# 5_cyber60-mxhs_periferals.net
KiCad netlist of a schematic drawn in Altium Designer
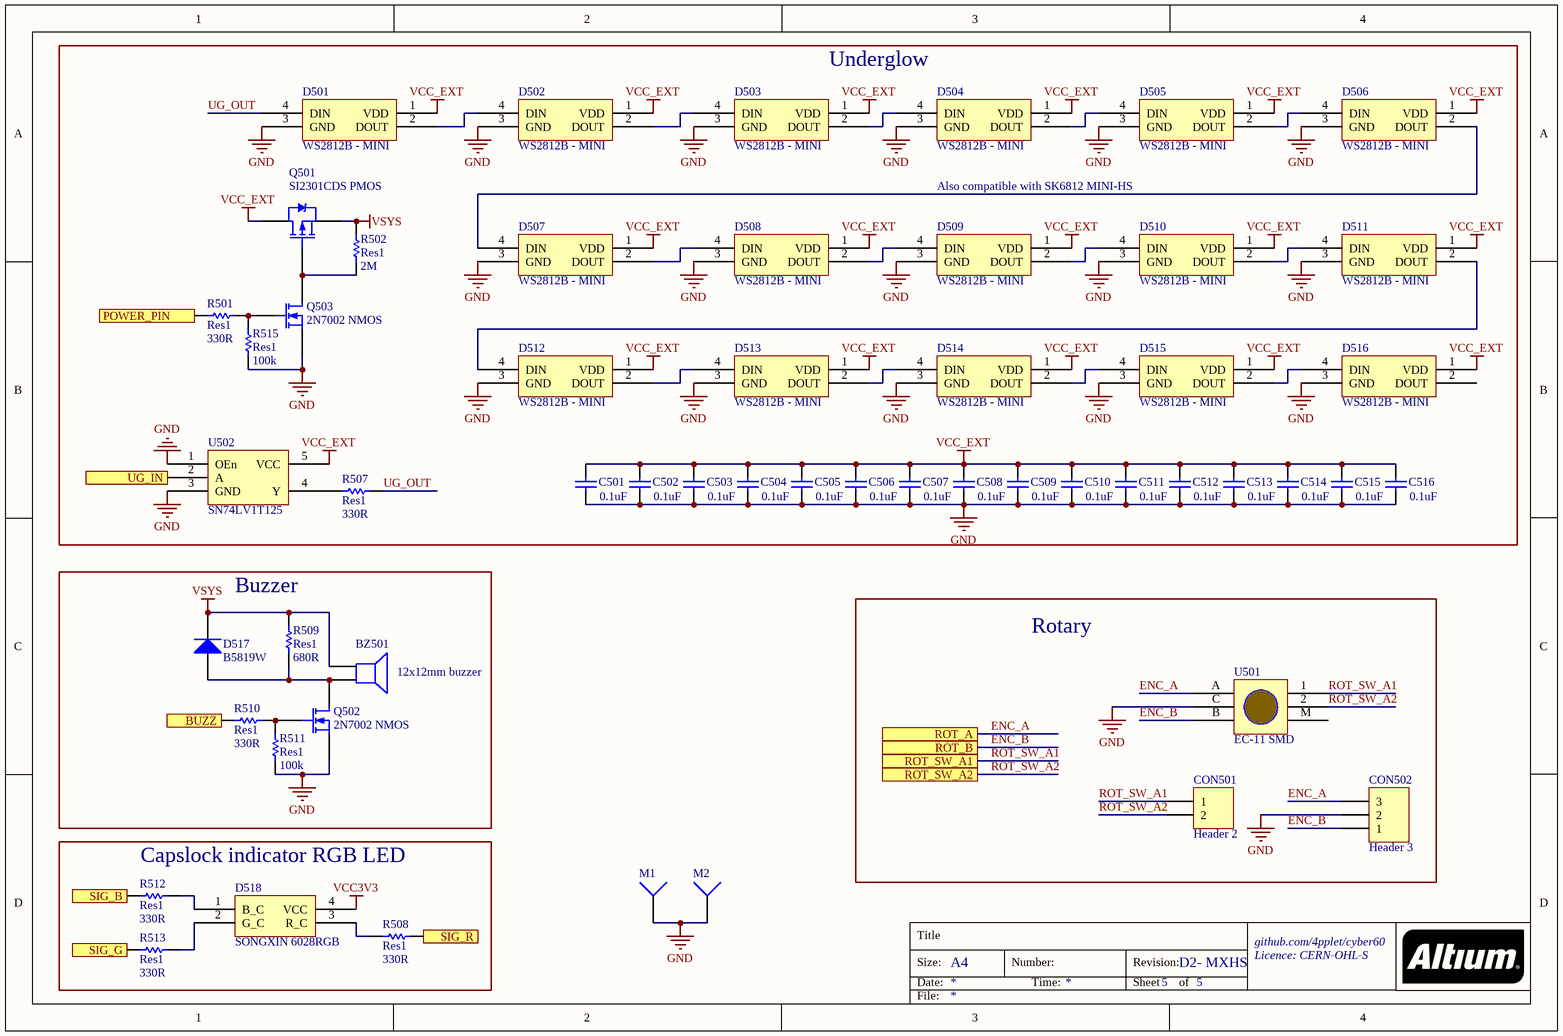
[diagram p0: 5_cyber60-mxhs_periferals.SchDoc]

(export (version "E")
  (design (tool "Eeschema 10.0.6"))
  (components
    (comp (ref "BZ501")
      (value "12x12mm buzzer")
      (footprint "buzzer 12x12")
      (description "Loudspeaker")
      (fields (field (name "LCSC PART #") "C409829") (field (name "MRF.PART") "YS-SBZ1230"))
      (libsource (lib "Miscellaneous Devices") (part "Speaker"))
    )
    (comp (ref "C501")
      (value "0.1uF")
      (footprint "C0603[1608]")
      (description "Capacitor")
      (fields (field (name "MFG") "KEMET") (field (name "LCSC PART #") "C14663"))
      (libsource (lib "Miscellaneous Devices") (part "Cap"))
    )
    (comp (ref "C502")
      (value "0.1uF")
      (footprint "C0603[1608]")
      (description "Capacitor")
      (fields (field (name "MFG") "KEMET") (field (name "LCSC PART #") "C14663"))
      (libsource (lib "Miscellaneous Devices") (part "Cap"))
    )
    (comp (ref "C503")
      (value "0.1uF")
      (footprint "C0603[1608]")
      (description "Capacitor")
      (fields (field (name "MFG") "KEMET") (field (name "LCSC PART #") "C14663"))
      (libsource (lib "Miscellaneous Devices") (part "Cap"))
    )
    (comp (ref "C504")
      (value "0.1uF")
      (footprint "C0603[1608]")
      (description "Capacitor")
      (fields (field (name "MFG") "KEMET") (field (name "LCSC PART #") "C14663"))
      (libsource (lib "Miscellaneous Devices") (part "Cap"))
    )
    (comp (ref "C505")
      (value "0.1uF")
      (footprint "C0603[1608]")
      (description "Capacitor")
      (fields (field (name "MFG") "KEMET") (field (name "LCSC PART #") "C14663"))
      (libsource (lib "Miscellaneous Devices") (part "Cap"))
    )
    (comp (ref "C506")
      (value "0.1uF")
      (footprint "C0603[1608]")
      (description "Capacitor")
      (fields (field (name "MFG") "KEMET") (field (name "LCSC PART #") "C14663"))
      (libsource (lib "Miscellaneous Devices") (part "Cap"))
    )
    (comp (ref "C507")
      (value "0.1uF")
      (footprint "C0603[1608]")
      (description "Capacitor")
      (fields (field (name "MFG") "KEMET") (field (name "LCSC PART #") "C14663"))
      (libsource (lib "Miscellaneous Devices") (part "Cap"))
    )
    (comp (ref "C508")
      (value "0.1uF")
      (footprint "C0603[1608]")
      (description "Capacitor")
      (fields (field (name "MFG") "KEMET") (field (name "LCSC PART #") "C14663"))
      (libsource (lib "Miscellaneous Devices") (part "Cap"))
    )
    (comp (ref "C509")
      (value "0.1uF")
      (footprint "C0603[1608]")
      (description "Capacitor")
      (fields (field (name "MFG") "KEMET") (field (name "LCSC PART #") "C14663"))
      (libsource (lib "Miscellaneous Devices") (part "Cap"))
    )
    (comp (ref "C510")
      (value "0.1uF")
      (footprint "C0603[1608]")
      (description "Capacitor")
      (fields (field (name "MFG") "KEMET") (field (name "LCSC PART #") "C14663"))
      (libsource (lib "Miscellaneous Devices") (part "Cap"))
    )
    (comp (ref "C511")
      (value "0.1uF")
      (footprint "C0603[1608]")
      (description "Capacitor")
      (fields (field (name "MFG") "KEMET") (field (name "LCSC PART #") "C14663"))
      (libsource (lib "Miscellaneous Devices") (part "Cap"))
    )
    (comp (ref "C512")
      (value "0.1uF")
      (footprint "C0603[1608]")
      (description "Capacitor")
      (fields (field (name "MFG") "KEMET") (field (name "LCSC PART #") "C14663"))
      (libsource (lib "Miscellaneous Devices") (part "Cap"))
    )
    (comp (ref "C513")
      (value "0.1uF")
      (footprint "C0603[1608]")
      (description "Capacitor")
      (fields (field (name "MFG") "KEMET") (field (name "LCSC PART #") "C14663"))
      (libsource (lib "Miscellaneous Devices") (part "Cap"))
    )
    (comp (ref "C514")
      (value "0.1uF")
      (footprint "C0603[1608]")
      (description "Capacitor")
      (fields (field (name "MFG") "KEMET") (field (name "LCSC PART #") "C14663"))
      (libsource (lib "Miscellaneous Devices") (part "Cap"))
    )
    (comp (ref "C515")
      (value "0.1uF")
      (footprint "C0603[1608]")
      (description "Capacitor")
      (fields (field (name "MFG") "KEMET") (field (name "LCSC PART #") "C14663"))
      (libsource (lib "Miscellaneous Devices") (part "Cap"))
    )
    (comp (ref "C516")
      (value "0.1uF")
      (footprint "C0603[1608]")
      (description "Capacitor")
      (fields (field (name "MFG") "KEMET") (field (name "LCSC PART #") "C14663"))
      (libsource (lib "Miscellaneous Devices") (part "Cap"))
    )
    (comp (ref "CON501")
      (value "Header 2")
      (footprint "HDR1X2")
      (description "Header, 2-Pin")
      (libsource (lib "Miscellaneous Connectors") (part "Header 2"))
    )
    (comp (ref "CON502")
      (value "Header 3")
      (footprint "HDR1X3")
      (description "Header, 3-Pin")
      (libsource (lib "Miscellaneous Connectors") (part "Header 3"))
    )
    (comp (ref "D501")
      (value "WS2812B - MINI")
      (footprint "WS2812B - 2020")
      (fields (field (name "LCSC PART #") "C965556") (field (name "MRF.PART") "WS2812C-2020"))
      (libsource (lib "Keebs") (part "WS2812B"))
    )
    (comp (ref "D502")
      (value "WS2812B - MINI")
      (footprint "WS2812B - 2020")
      (fields (field (name "LCSC PART #") "C965556") (field (name "MRF.PART") "WS2812C-2020"))
      (libsource (lib "Keebs") (part "WS2812B"))
    )
    (comp (ref "D503")
      (value "WS2812B - MINI")
      (footprint "WS2812B - 2020")
      (fields (field (name "LCSC PART #") "C965556") (field (name "MRF.PART") "WS2812C-2020"))
      (libsource (lib "Keebs") (part "WS2812B"))
    )
    (comp (ref "D504")
      (value "WS2812B - MINI")
      (footprint "WS2812B - 2020")
      (fields (field (name "LCSC PART #") "C965556") (field (name "MRF.PART") "WS2812C-2020"))
      (libsource (lib "Keebs") (part "WS2812B"))
    )
    (comp (ref "D505")
      (value "WS2812B - MINI")
      (footprint "WS2812B - 2020")
      (fields (field (name "LCSC PART #") "C965556") (field (name "MRF.PART") "WS2812C-2020"))
      (libsource (lib "Keebs") (part "WS2812B"))
    )
    (comp (ref "D506")
      (value "WS2812B - MINI")
      (footprint "WS2812B - 2020")
      (fields (field (name "LCSC PART #") "C965556") (field (name "MRF.PART") "WS2812C-2020"))
      (libsource (lib "Keebs") (part "WS2812B"))
    )
    (comp (ref "D507")
      (value "WS2812B - MINI")
      (footprint "WS2812B - 2020")
      (fields (field (name "LCSC PART #") "C965556") (field (name "MRF.PART") "WS2812C-2020"))
      (libsource (lib "Keebs") (part "WS2812B"))
    )
    (comp (ref "D508")
      (value "WS2812B - MINI")
      (footprint "WS2812B - 2020")
      (fields (field (name "LCSC PART #") "C965556") (field (name "MRF.PART") "WS2812C-2020"))
      (libsource (lib "Keebs") (part "WS2812B"))
    )
    (comp (ref "D509")
      (value "WS2812B - MINI")
      (footprint "WS2812B - 2020")
      (fields (field (name "LCSC PART #") "C965556") (field (name "MRF.PART") "WS2812C-2020"))
      (libsource (lib "Keebs") (part "WS2812B"))
    )
    (comp (ref "D510")
      (value "WS2812B - MINI")
      (footprint "WS2812B - 2020")
      (fields (field (name "LCSC PART #") "C965556") (field (name "MRF.PART") "WS2812C-2020"))
      (libsource (lib "Keebs") (part "WS2812B"))
    )
    (comp (ref "D511")
      (value "WS2812B - MINI")
      (footprint "WS2812B - 2020")
      (fields (field (name "LCSC PART #") "C965556") (field (name "MRF.PART") "WS2812C-2020"))
      (libsource (lib "Keebs") (part "WS2812B"))
    )
    (comp (ref "D512")
      (value "WS2812B - MINI")
      (footprint "WS2812B - 2020")
      (fields (field (name "LCSC PART #") "C965556") (field (name "MRF.PART") "WS2812C-2020"))
      (libsource (lib "Keebs") (part "WS2812B"))
    )
    (comp (ref "D513")
      (value "WS2812B - MINI")
      (footprint "WS2812B - 2020")
      (fields (field (name "LCSC PART #") "C965556") (field (name "MRF.PART") "WS2812C-2020"))
      (libsource (lib "Keebs") (part "WS2812B"))
    )
    (comp (ref "D514")
      (value "WS2812B - MINI")
      (footprint "WS2812B - 2020")
      (fields (field (name "LCSC PART #") "C965556") (field (name "MRF.PART") "WS2812C-2020"))
      (libsource (lib "Keebs") (part "WS2812B"))
    )
    (comp (ref "D515")
      (value "WS2812B - MINI")
      (footprint "WS2812B - 2020")
      (fields (field (name "LCSC PART #") "C965556") (field (name "MRF.PART") "WS2812C-2020"))
      (libsource (lib "Keebs") (part "WS2812B"))
    )
    (comp (ref "D516")
      (value "WS2812B - MINI")
      (footprint "WS2812B - 2020")
      (fields (field (name "LCSC PART #") "C965556") (field (name "MRF.PART") "WS2812C-2020"))
      (libsource (lib "Keebs") (part "WS2812B"))
    )
    (comp (ref "D517")
      (value "B5819W")
      (footprint "SOD-123")
      (description "Default Diode")
      (fields (field (name "LCSC PART #") "C8598"))
      (libsource (lib "Miscellaneous Devices") (part "Diode"))
    )
    (comp (ref "D518")
      (value "SONGXIN 6028RGB")
      (footprint "SONGXIN 6028RGB - shaped")
      (libsource (lib "Keebs") (part "SONGXIN 6028RGB"))
    )
    (comp (ref "M1")
      (value "Socket")
      (footprint "mounting_hole")
      (fields (field (name "PUBLISHER") "Altium Limited"))
      (libsource (lib "Miscellaneous Connectors") (part "Socket"))
    )
    (comp (ref "M2")
      (value "Socket")
      (footprint "mounting_hole")
      (fields (field (name "PUBLISHER") "Altium Limited"))
      (libsource (lib "Miscellaneous Connectors") (part "Socket"))
    )
    (comp (ref "Q501")
      (value "SI2301CDS PMOS")
      (footprint "SOT-23-3")
      (description "P-Channel Power MOSFET")
      (fields (field (name "MRF.PART") "SI2301CDS-T1-GE3") (field (name "LCSC PART #") "C10487"))
      (libsource (lib "Miscellaneous Devices") (part "PMOS-2"))
    )
    (comp (ref "Q502")
      (value "2N7002 NMOS")
      (footprint "SOT-23-3")
      (description "N-Channel MOSFET")
      (fields (field (name "LCSC PART #") "C8545") (field (name "MRF.PART") "2N7002"))
      (libsource (lib "Miscellaneous Devices") (part "MOSFET-N"))
    )
    (comp (ref "Q503")
      (value "2N7002 NMOS")
      (footprint "SOT-23-3")
      (description "N-Channel MOSFET")
      (fields (field (name "LCSC PART #") "C8545") (field (name "MRF.PART") "2N7002"))
      (libsource (lib "Miscellaneous Devices") (part "MOSFET-N"))
    )
    (comp (ref "R501")
      (value "Res1")
      (footprint "R0603[1608]")
      (description "Resistor")
      (fields
        (field (name "ALTIUM_VALUE") "330R")
        (field (name "LCSC PART #") "C23138")
        (field (name "MRF.PART") "0603WAF3300T5E")
      )
      (libsource (lib "Miscellaneous Devices") (part "Res1"))
    )
    (comp (ref "R502")
      (value "Res1")
      (footprint "R0603[1608]")
      (description "Resistor")
      (fields
        (field (name "ALTIUM_VALUE") "2M")
        (field (name "MRF.PART") "0603WAF2004T5E")
        (field (name "LCSC PART #") "C22976")
      )
      (libsource (lib "Miscellaneous Devices") (part "Res1"))
    )
    (comp (ref "R507")
      (value "Res1")
      (footprint "R0603[1608]")
      (description "Resistor")
      (fields
        (field (name "ALTIUM_VALUE") "330R")
        (field (name "LCSC PART #") "C23138")
        (field (name "MRF.PART") "0603WAF3300T5E")
      )
      (libsource (lib "Miscellaneous Devices") (part "Res1"))
    )
    (comp (ref "R508")
      (value "Res1")
      (footprint "R0603[1608]")
      (description "Resistor")
      (fields
        (field (name "ALTIUM_VALUE") "330R")
        (field (name "LCSC PART #") "C23138")
        (field (name "MRF.PART") "0603WAF3300T5E")
      )
      (libsource (lib "Miscellaneous Devices") (part "Res1"))
    )
    (comp (ref "R509")
      (value "Res1")
      (footprint "R0603[1608]")
      (description "Resistor")
      (fields
        (field (name "ALTIUM_VALUE") "680R")
        (field (name "MRF.PART") "0603WAF6800T5E")
        (field (name "LCSC PART #") "C23228")
      )
      (libsource (lib "Miscellaneous Devices") (part "Res1"))
    )
    (comp (ref "R510")
      (value "Res1")
      (footprint "R0603[1608]")
      (description "Resistor")
      (fields
        (field (name "ALTIUM_VALUE") "330R")
        (field (name "LCSC PART #") "C23138")
        (field (name "MRF.PART") "0603WAF3300T5E")
      )
      (libsource (lib "Miscellaneous Devices") (part "Res1"))
    )
    (comp (ref "R511")
      (value "Res1")
      (footprint "R0603[1608]")
      (description "Resistor")
      (fields
        (field (name "ALTIUM_VALUE") "100k")
        (field (name "MRF.PART") "0603WAF1003T5E")
        (field (name "LCSC PART #") "C25803")
      )
      (libsource (lib "Miscellaneous Devices") (part "Res1"))
    )
    (comp (ref "R512")
      (value "Res1")
      (footprint "R0603[1608]")
      (description "Resistor")
      (fields
        (field (name "ALTIUM_VALUE") "330R")
        (field (name "LCSC PART #") "C23138")
        (field (name "MRF.PART") "0603WAF3300T5E")
      )
      (libsource (lib "Miscellaneous Devices") (part "Res1"))
    )
    (comp (ref "R513")
      (value "Res1")
      (footprint "R0603[1608]")
      (description "Resistor")
      (fields
        (field (name "ALTIUM_VALUE") "330R")
        (field (name "LCSC PART #") "C23138")
        (field (name "MRF.PART") "0603WAF3300T5E")
      )
      (libsource (lib "Miscellaneous Devices") (part "Res1"))
    )
    (comp (ref "R515")
      (value "Res1")
      (footprint "R0603[1608]")
      (description "Resistor")
      (fields
        (field (name "ALTIUM_VALUE") "100k")
        (field (name "MRF.PART") "0603WAF1003T5E")
        (field (name "LCSC PART #") "C25803")
      )
      (libsource (lib "Miscellaneous Devices") (part "Res1"))
    )
    (comp (ref "U501") (value "EC-11 SMD") (footprint "EC11-SMD") (libsource (lib "Keebs") (part "EC-11")))
    (comp (ref "U502")
      (value "SN74LV1T125")
      (footprint "SOT-23-5")
      (description "SN74LV1T125 or SN74LV1T34. Connect OE to GND")
      (fields (field (name "LCSC PART #") "C473338") (field (name "MRF.PART") "SN74LV1T125DBVR"))
      (libsource (lib "Keebs") (part "SN74LV1T125"))
    )
  )
  (nets
    (net (code "1") (name "/BUZZ") (class "Default")
      (node (ref "R510") (pin "2") (pinfunction "2_2") (pintype "passive"))
    )
    (net (code "2") (name "/ENC_A") (class "Default")
      (node (ref "CON502") (pin "3") (pinfunction "3_3") (pintype "passive"))
      (node (ref "U501") (pin "A") (pinfunction "B_A") (pintype "passive"))
    )
    (net (code "3") (name "/ENC_B") (class "Default")
      (node (ref "CON502") (pin "1") (pinfunction "1_1") (pintype "passive"))
      (node (ref "U501") (pin "B") (pinfunction "B_B") (pintype "passive"))
    )
    (net (code "4") (name "/POWER_PIN") (class "Default")
      (node (ref "R501") (pin "1") (pinfunction "1_1") (pintype "passive"))
    )
    (net (code "5") (name "/ROT_SW_A1") (class "Default")
      (node (ref "CON501") (pin "1") (pinfunction "1_1") (pintype "passive"))
      (node (ref "U501") (pin "1") (pinfunction "1_1") (pintype "passive"))
    )
    (net (code "6") (name "/ROT_SW_A2") (class "Default")
      (node (ref "CON501") (pin "2") (pinfunction "2_2") (pintype "passive"))
      (node (ref "U501") (pin "2") (pinfunction "2_2") (pintype "passive"))
    )
    (net (code "7") (name "/SIG_B") (class "Default")
      (node (ref "R512") (pin "2") (pinfunction "2_2") (pintype "passive"))
    )
    (net (code "8") (name "/SIG_G") (class "Default")
      (node (ref "R513") (pin "2") (pinfunction "2_2") (pintype "passive"))
    )
    (net (code "9") (name "/SIG_R") (class "Default")
      (node (ref "R508") (pin "1") (pinfunction "1_1") (pintype "passive"))
    )
    (net (code "10") (name "/UG_IN") (class "Default")
      (node (ref "U502") (pin "2") (pinfunction "A_2") (pintype "passive"))
    )
    (net (code "11") (name "/UG_OUT") (class "Default")
      (node (ref "D501") (pin "4") (pinfunction "DIN_4") (pintype "passive"))
      (node (ref "R507") (pin "1") (pinfunction "1_1") (pintype "passive"))
    )
    (net (code "12") (name "GND") (class "Default")
      (node (ref "C501") (pin "1") (pinfunction "1_1") (pintype "passive"))
      (node (ref "C502") (pin "1") (pinfunction "1_1") (pintype "passive"))
      (node (ref "C503") (pin "1") (pinfunction "1_1") (pintype "passive"))
      (node (ref "C504") (pin "1") (pinfunction "1_1") (pintype "passive"))
      (node (ref "C505") (pin "1") (pinfunction "1_1") (pintype "passive"))
      (node (ref "C506") (pin "1") (pinfunction "1_1") (pintype "passive"))
      (node (ref "C507") (pin "1") (pinfunction "1_1") (pintype "passive"))
      (node (ref "C508") (pin "1") (pinfunction "1_1") (pintype "passive"))
      (node (ref "C509") (pin "1") (pinfunction "1_1") (pintype "passive"))
      (node (ref "C510") (pin "1") (pinfunction "1_1") (pintype "passive"))
      (node (ref "C511") (pin "1") (pinfunction "1_1") (pintype "passive"))
      (node (ref "C512") (pin "1") (pinfunction "1_1") (pintype "passive"))
      (node (ref "C513") (pin "1") (pinfunction "1_1") (pintype "passive"))
      (node (ref "C514") (pin "1") (pinfunction "1_1") (pintype "passive"))
      (node (ref "C515") (pin "1") (pinfunction "1_1") (pintype "passive"))
      (node (ref "C516") (pin "1") (pinfunction "1_1") (pintype "passive"))
      (node (ref "CON502") (pin "2") (pinfunction "2_2") (pintype "passive"))
      (node (ref "D501") (pin "3") (pinfunction "GND_3") (pintype "passive"))
      (node (ref "D502") (pin "3") (pinfunction "GND_3") (pintype "passive"))
      (node (ref "D503") (pin "3") (pinfunction "GND_3") (pintype "passive"))
      (node (ref "D504") (pin "3") (pinfunction "GND_3") (pintype "passive"))
      (node (ref "D505") (pin "3") (pinfunction "GND_3") (pintype "passive"))
      (node (ref "D506") (pin "3") (pinfunction "GND_3") (pintype "passive"))
      (node (ref "D507") (pin "3") (pinfunction "GND_3") (pintype "passive"))
      (node (ref "D508") (pin "3") (pinfunction "GND_3") (pintype "passive"))
      (node (ref "D509") (pin "3") (pinfunction "GND_3") (pintype "passive"))
      (node (ref "D510") (pin "3") (pinfunction "GND_3") (pintype "passive"))
      (node (ref "D511") (pin "3") (pinfunction "GND_3") (pintype "passive"))
      (node (ref "D512") (pin "3") (pinfunction "GND_3") (pintype "passive"))
      (node (ref "D513") (pin "3") (pinfunction "GND_3") (pintype "passive"))
      (node (ref "D514") (pin "3") (pinfunction "GND_3") (pintype "passive"))
      (node (ref "D515") (pin "3") (pinfunction "GND_3") (pintype "passive"))
      (node (ref "D516") (pin "3") (pinfunction "GND_3") (pintype "passive"))
      (node (ref "M1") (pin "1") (pinfunction "1_1") (pintype "passive"))
      (node (ref "M2") (pin "1") (pinfunction "1_1") (pintype "passive"))
      (node (ref "Q502") (pin "2") (pinfunction "S_2") (pintype "passive"))
      (node (ref "Q503") (pin "2") (pinfunction "S_2") (pintype "passive"))
      (node (ref "R511") (pin "2") (pinfunction "2_2") (pintype "passive"))
      (node (ref "R515") (pin "2") (pinfunction "2_2") (pintype "passive"))
      (node (ref "U501") (pin "C") (pinfunction "C_C") (pintype "passive"))
      (node (ref "U502") (pin "1") (pinfunction "OEn_1") (pintype "passive"))
      (node (ref "U502") (pin "3") (pinfunction "GND_3") (pintype "passive"))
    )
    (net (code "13") (name "Net-(D501-DOUT)") (class "Default")
      (node (ref "D501") (pin "2") (pinfunction "DOUT_2") (pintype "passive"))
      (node (ref "D502") (pin "4") (pinfunction "DIN_4") (pintype "passive"))
    )
    (net (code "14") (name "Net-(D502-DOUT)") (class "Default")
      (node (ref "D502") (pin "2") (pinfunction "DOUT_2") (pintype "passive"))
      (node (ref "D503") (pin "4") (pinfunction "DIN_4") (pintype "passive"))
    )
    (net (code "15") (name "Net-(D503-DOUT)") (class "Default")
      (node (ref "D503") (pin "2") (pinfunction "DOUT_2") (pintype "passive"))
      (node (ref "D504") (pin "4") (pinfunction "DIN_4") (pintype "passive"))
    )
    (net (code "16") (name "Net-(D504-DOUT)") (class "Default")
      (node (ref "D504") (pin "2") (pinfunction "DOUT_2") (pintype "passive"))
      (node (ref "D505") (pin "4") (pinfunction "DIN_4") (pintype "passive"))
    )
    (net (code "17") (name "Net-(D505-DOUT)") (class "Default")
      (node (ref "D505") (pin "2") (pinfunction "DOUT_2") (pintype "passive"))
      (node (ref "D506") (pin "4") (pinfunction "DIN_4") (pintype "passive"))
    )
    (net (code "18") (name "Net-(D506-DOUT)") (class "Default")
      (node (ref "D506") (pin "2") (pinfunction "DOUT_2") (pintype "passive"))
      (node (ref "D507") (pin "4") (pinfunction "DIN_4") (pintype "passive"))
    )
    (net (code "19") (name "Net-(D507-DOUT)") (class "Default")
      (node (ref "D507") (pin "2") (pinfunction "DOUT_2") (pintype "passive"))
      (node (ref "D508") (pin "4") (pinfunction "DIN_4") (pintype "passive"))
    )
    (net (code "20") (name "Net-(D508-DOUT)") (class "Default")
      (node (ref "D508") (pin "2") (pinfunction "DOUT_2") (pintype "passive"))
      (node (ref "D509") (pin "4") (pinfunction "DIN_4") (pintype "passive"))
    )
    (net (code "21") (name "Net-(D509-DOUT)") (class "Default")
      (node (ref "D509") (pin "2") (pinfunction "DOUT_2") (pintype "passive"))
      (node (ref "D510") (pin "4") (pinfunction "DIN_4") (pintype "passive"))
    )
    (net (code "22") (name "Net-(D510-DOUT)") (class "Default")
      (node (ref "D510") (pin "2") (pinfunction "DOUT_2") (pintype "passive"))
      (node (ref "D511") (pin "4") (pinfunction "DIN_4") (pintype "passive"))
    )
    (net (code "23") (name "Net-(D511-DOUT)") (class "Default")
      (node (ref "D511") (pin "2") (pinfunction "DOUT_2") (pintype "passive"))
      (node (ref "D512") (pin "4") (pinfunction "DIN_4") (pintype "passive"))
    )
    (net (code "24") (name "Net-(D512-DOUT)") (class "Default")
      (node (ref "D512") (pin "2") (pinfunction "DOUT_2") (pintype "passive"))
      (node (ref "D513") (pin "4") (pinfunction "DIN_4") (pintype "passive"))
    )
    (net (code "25") (name "Net-(D513-DOUT)") (class "Default")
      (node (ref "D513") (pin "2") (pinfunction "DOUT_2") (pintype "passive"))
      (node (ref "D514") (pin "4") (pinfunction "DIN_4") (pintype "passive"))
    )
    (net (code "26") (name "Net-(D514-DOUT)") (class "Default")
      (node (ref "D514") (pin "2") (pinfunction "DOUT_2") (pintype "passive"))
      (node (ref "D515") (pin "4") (pinfunction "DIN_4") (pintype "passive"))
    )
    (net (code "27") (name "Net-(D515-DOUT)") (class "Default")
      (node (ref "D515") (pin "2") (pinfunction "DOUT_2") (pintype "passive"))
      (node (ref "D516") (pin "4") (pinfunction "DIN_4") (pintype "passive"))
    )
    (net (code "28") (name "Net-(D517-A)") (class "Default")
      (node (ref "BZ501") (pin "2") (pinfunction "2_2") (pintype "passive"))
      (node (ref "D517") (pin "1") (pinfunction "A_1") (pintype "passive"))
      (node (ref "Q502") (pin "3") (pinfunction "D_3") (pintype "passive"))
      (node (ref "R509") (pin "2") (pinfunction "2_2") (pintype "passive"))
    )
    (net (code "29") (name "Net-(D518-B_C)") (class "Default")
      (node (ref "D518") (pin "1") (pinfunction "B_C_1") (pintype "passive"))
      (node (ref "R512") (pin "1") (pinfunction "1_1") (pintype "passive"))
    )
    (net (code "30") (name "Net-(D518-G_C)") (class "Default")
      (node (ref "D518") (pin "2") (pinfunction "G_C_2") (pintype "passive"))
      (node (ref "R513") (pin "1") (pinfunction "1_1") (pintype "passive"))
    )
    (net (code "31") (name "Net-(D518-R_C)") (class "Default")
      (node (ref "D518") (pin "3") (pinfunction "R_C_3") (pintype "passive"))
      (node (ref "R508") (pin "2") (pinfunction "2_2") (pintype "passive"))
    )
    (net (code "32") (name "Net-(Q501-G)") (class "Default")
      (node (ref "Q501") (pin "1") (pinfunction "G_1") (pintype "passive"))
      (node (ref "Q503") (pin "3") (pinfunction "D_3") (pintype "passive"))
      (node (ref "R502") (pin "1") (pinfunction "1_1") (pintype "passive"))
    )
    (net (code "33") (name "Net-(Q502-G)") (class "Default")
      (node (ref "Q502") (pin "1") (pinfunction "G_1") (pintype "passive"))
      (node (ref "R510") (pin "1") (pinfunction "1_1") (pintype "passive"))
      (node (ref "R511") (pin "1") (pinfunction "1_1") (pintype "passive"))
    )
    (net (code "34") (name "Net-(Q503-G)") (class "Default")
      (node (ref "Q503") (pin "1") (pinfunction "G_1") (pintype "passive"))
      (node (ref "R501") (pin "2") (pinfunction "2_2") (pintype "passive"))
      (node (ref "R515") (pin "1") (pinfunction "1_1") (pintype "passive"))
    )
    (net (code "35") (name "Net-(U502-Y)") (class "Default")
      (node (ref "R507") (pin "2") (pinfunction "2_2") (pintype "passive"))
      (node (ref "U502") (pin "4") (pinfunction "Y_4") (pintype "passive"))
    )
    (net (code "36") (name "VCC3V3") (class "Default")
      (node (ref "D518") (pin "4") (pinfunction "VCC_4") (pintype "passive"))
    )
    (net (code "37") (name "VCC_EXT") (class "Default")
      (node (ref "C501") (pin "2") (pinfunction "2_2") (pintype "passive"))
      (node (ref "C502") (pin "2") (pinfunction "2_2") (pintype "passive"))
      (node (ref "C503") (pin "2") (pinfunction "2_2") (pintype "passive"))
      (node (ref "C504") (pin "2") (pinfunction "2_2") (pintype "passive"))
      (node (ref "C505") (pin "2") (pinfunction "2_2") (pintype "passive"))
      (node (ref "C506") (pin "2") (pinfunction "2_2") (pintype "passive"))
      (node (ref "C507") (pin "2") (pinfunction "2_2") (pintype "passive"))
      (node (ref "C508") (pin "2") (pinfunction "2_2") (pintype "passive"))
      (node (ref "C509") (pin "2") (pinfunction "2_2") (pintype "passive"))
      (node (ref "C510") (pin "2") (pinfunction "2_2") (pintype "passive"))
      (node (ref "C511") (pin "2") (pinfunction "2_2") (pintype "passive"))
      (node (ref "C512") (pin "2") (pinfunction "2_2") (pintype "passive"))
      (node (ref "C513") (pin "2") (pinfunction "2_2") (pintype "passive"))
      (node (ref "C514") (pin "2") (pinfunction "2_2") (pintype "passive"))
      (node (ref "C515") (pin "2") (pinfunction "2_2") (pintype "passive"))
      (node (ref "C516") (pin "2") (pinfunction "2_2") (pintype "passive"))
      (node (ref "D501") (pin "1") (pinfunction "VDD_1") (pintype "passive"))
      (node (ref "D502") (pin "1") (pinfunction "VDD_1") (pintype "passive"))
      (node (ref "D503") (pin "1") (pinfunction "VDD_1") (pintype "passive"))
      (node (ref "D504") (pin "1") (pinfunction "VDD_1") (pintype "passive"))
      (node (ref "D505") (pin "1") (pinfunction "VDD_1") (pintype "passive"))
      (node (ref "D506") (pin "1") (pinfunction "VDD_1") (pintype "passive"))
      (node (ref "D507") (pin "1") (pinfunction "VDD_1") (pintype "passive"))
      (node (ref "D508") (pin "1") (pinfunction "VDD_1") (pintype "passive"))
      (node (ref "D509") (pin "1") (pinfunction "VDD_1") (pintype "passive"))
      (node (ref "D510") (pin "1") (pinfunction "VDD_1") (pintype "passive"))
      (node (ref "D511") (pin "1") (pinfunction "VDD_1") (pintype "passive"))
      (node (ref "D512") (pin "1") (pinfunction "VDD_1") (pintype "passive"))
      (node (ref "D513") (pin "1") (pinfunction "VDD_1") (pintype "passive"))
      (node (ref "D514") (pin "1") (pinfunction "VDD_1") (pintype "passive"))
      (node (ref "D515") (pin "1") (pinfunction "VDD_1") (pintype "passive"))
      (node (ref "D516") (pin "1") (pinfunction "VDD_1") (pintype "passive"))
      (node (ref "Q501") (pin "3") (pinfunction "D_3") (pintype "passive"))
      (node (ref "U502") (pin "5") (pinfunction "VCC_5") (pintype "passive"))
    )
    (net (code "38") (name "VSYS") (class "Default")
      (node (ref "BZ501") (pin "1") (pinfunction "1_1") (pintype "passive"))
      (node (ref "D517") (pin "2") (pinfunction "K_2") (pintype "passive"))
      (node (ref "Q501") (pin "2") (pinfunction "S_2") (pintype "passive"))
      (node (ref "R502") (pin "2") (pinfunction "2_2") (pintype "passive"))
      (node (ref "R509") (pin "1") (pinfunction "1_1") (pintype "passive"))
    )
    (net (code "39") (name "unconnected-(D516-DOUT-Pad2)") (class "Default")
      (node (ref "D516") (pin "2") (pinfunction "DOUT_2") (pintype "passive"))
    )
    (net (code "40") (name "unconnected-(U501-PadM)") (class "Default")
      (node (ref "U501") (pin "M") (pinfunction "M_M") (pintype "passive"))
    )
  )
)
